# Ring_opto_interface_v2.net
KiCad netlist of a schematic drawn in EAGLE
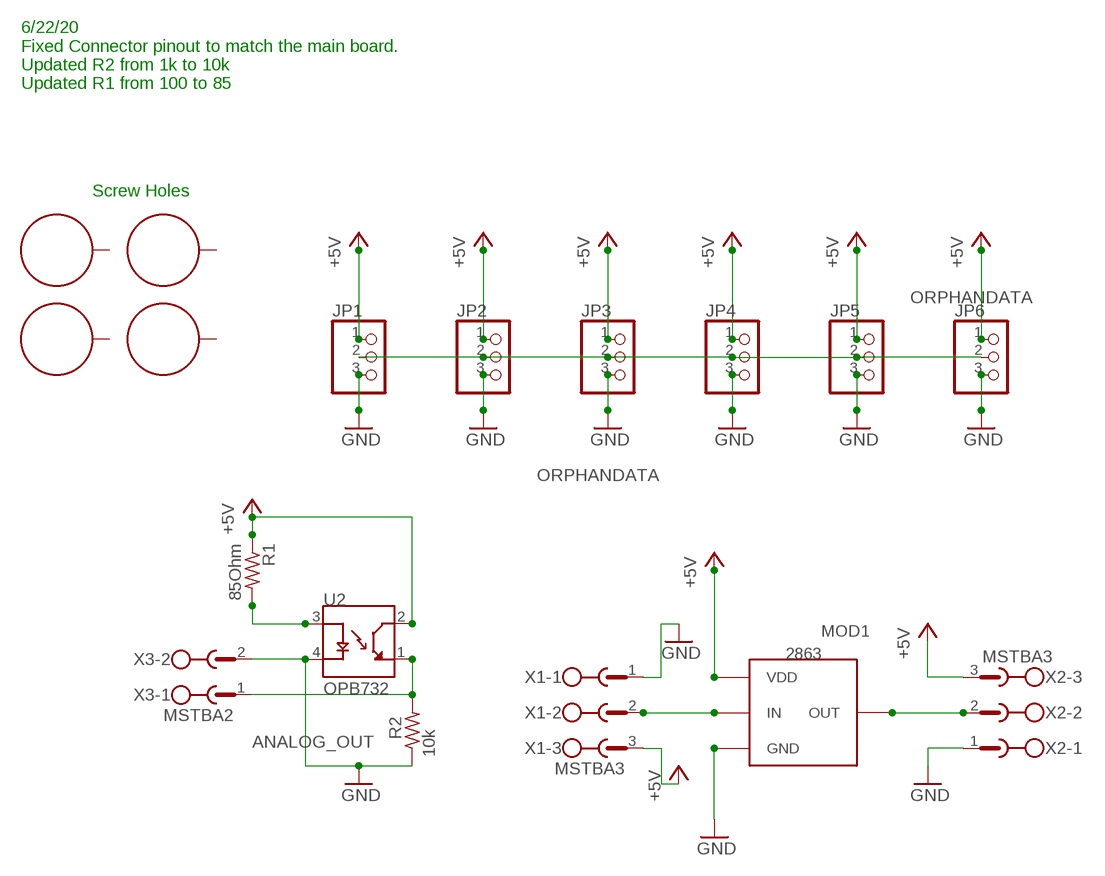
[diagram p0: schematic, sheet 1]

(export (version "E")
  (design (tool "Eeschema 10.0.6"))
  (components
    (comp (ref "H1")
      (value "STANDOFF_ELECTRICAL5-32")
      (footprint "eagle-import:STANDOFF_ELECTRICAL_5_32")
      (libsource (lib "eagle-import") (part "STANDOFF_ELECTRICAL5-32"))
    )
    (comp (ref "H2")
      (value "STANDOFF_ELECTRICAL5-32")
      (footprint "eagle-import:STANDOFF_ELECTRICAL_5_32")
      (libsource (lib "eagle-import") (part "STANDOFF_ELECTRICAL5-32"))
    )
    (comp (ref "H3")
      (value "STANDOFF_ELECTRICAL5-32")
      (footprint "eagle-import:STANDOFF_ELECTRICAL_5_32")
      (libsource (lib "eagle-import") (part "STANDOFF_ELECTRICAL5-32"))
    )
    (comp (ref "H4")
      (value "STANDOFF_ELECTRICAL5-32")
      (footprint "eagle-import:STANDOFF_ELECTRICAL_5_32")
      (libsource (lib "eagle-import") (part "STANDOFF_ELECTRICAL5-32"))
    )
    (comp (ref "JP1")
      (value "PINHD-1X3CB")
      (footprint "eagle-import:1X03-CLEANBIG")
      (libsource (lib "eagle-import") (part "PINHD-1X3CB"))
    )
    (comp (ref "JP2")
      (value "PINHD-1X3CB")
      (footprint "eagle-import:1X03-CLEANBIG")
      (libsource (lib "eagle-import") (part "PINHD-1X3CB"))
    )
    (comp (ref "JP3")
      (value "PINHD-1X3CB")
      (footprint "eagle-import:1X03-CLEANBIG")
      (libsource (lib "eagle-import") (part "PINHD-1X3CB"))
    )
    (comp (ref "JP4")
      (value "PINHD-1X3CB")
      (footprint "eagle-import:1X03-CLEANBIG")
      (libsource (lib "eagle-import") (part "PINHD-1X3CB"))
    )
    (comp (ref "JP5")
      (value "PINHD-1X3CB")
      (footprint "eagle-import:1X03-CLEANBIG")
      (libsource (lib "eagle-import") (part "PINHD-1X3CB"))
    )
    (comp (ref "JP6")
      (value "PINHD-1X3CB")
      (footprint "eagle-import:1X03-CLEANBIG")
      (libsource (lib "eagle-import") (part "PINHD-1X3CB"))
    )
    (comp (ref "MOD1")
      (value "2863")
      (footprint "eagle-import:ADAFRUIT_2863")
      (fields (field (name "MF") "Adafruit"))
      (libsource (lib "eagle-import") (part "2863"))
    )
    (comp (ref "R1")
      (value "85Ohm")
      (footprint "eagle-import:RESAD1176W63L850D250B")
      (libsource (lib "eagle-import") (part "R-USAXIAL-11.7MM-PITCH_"))
    )
    (comp (ref "R2")
      (value "10k")
      (footprint "eagle-import:RESAD1176W63L850D250B")
      (libsource (lib "eagle-import") (part "R-USAXIAL-11.7MM-PITCH_"))
    )
    (comp (ref "U2")
      (value "OPB732")
      (footprint "eagle-import:OPTO_OPB732")
      (fields (field (name "MF") "TT Electronics/Optek"))
      (libsource (lib "eagle-import") (part "OPB732"))
    )
    (comp (ref "X1")
      (value "MSTBA3")
      (footprint "eagle-import:MSTBA3")
      (fields (field (name "MF") "FARNELL") (field (name "MPN") "1757255"))
      (libsource (lib "eagle-import") (part "MSTBA3"))
    )
    (comp (ref "X2")
      (value "MSTBA3")
      (footprint "eagle-import:MSTBA3")
      (fields (field (name "MF") "FARNELL") (field (name "MPN") "1757255"))
      (libsource (lib "eagle-import") (part "MSTBA3"))
    )
    (comp (ref "X3")
      (value "MSTBA2")
      (footprint "eagle-import:MSTBA2")
      (fields (field (name "MF") "FARNELL") (field (name "MPN") "1757242"))
      (libsource (lib "eagle-import") (part "MSTBA2"))
    )
  )
  (nets
    (net (code "1") (name "+5V") (class "Default")
      (node (ref "JP1") (pin "1") (pinfunction "1_1") (pintype "passive"))
      (node (ref "JP2") (pin "1") (pinfunction "1_1") (pintype "passive"))
      (node (ref "JP3") (pin "1") (pinfunction "1_1") (pintype "passive"))
      (node (ref "JP4") (pin "1") (pinfunction "1_1") (pintype "passive"))
      (node (ref "JP5") (pin "1") (pinfunction "1_1") (pintype "passive"))
      (node (ref "JP6") (pin "1") (pinfunction "1_1") (pintype "passive"))
      (node (ref "MOD1") (pin "VDD1") (pinfunction "VDD_VDD1") (pintype "power_in"))
      (node (ref "MOD1") (pin "VDD2") (pinfunction "VDD_VDD2") (pintype "power_in"))
      (node (ref "R1") (pin "1") (pinfunction "1_1") (pintype "passive"))
      (node (ref "U2") (pin "2") (pinfunction "CT_2") (pintype "passive"))
      (node (ref "X1") (pin "3") (pinfunction "1_3") (pintype "passive"))
      (node (ref "X2") (pin "3") (pinfunction "1_3") (pintype "passive"))
    )
    (net (code "2") (name "/ANALOG_OUT") (class "Default")
      (node (ref "R2") (pin "2") (pinfunction "2_2") (pintype "passive"))
      (node (ref "U2") (pin "1") (pinfunction "ET_1") (pintype "passive"))
      (node (ref "X3") (pin "1") (pinfunction "1_1") (pintype "passive"))
    )
    (net (code "3") (name "/ORPHANDATA") (class "Default")
      (node (ref "JP1") (pin "2") (pinfunction "2_2") (pintype "passive"))
      (node (ref "JP2") (pin "2") (pinfunction "2_2") (pintype "passive"))
      (node (ref "JP3") (pin "2") (pinfunction "2_2") (pintype "passive"))
      (node (ref "JP4") (pin "2") (pinfunction "2_2") (pintype "passive"))
      (node (ref "JP5") (pin "2") (pinfunction "2_2") (pintype "passive"))
      (node (ref "JP6") (pin "2") (pinfunction "2_2") (pintype "passive"))
    )
    (net (code "4") (name "GND") (class "Default")
      (node (ref "JP1") (pin "3") (pinfunction "3_3") (pintype "passive"))
      (node (ref "JP2") (pin "3") (pinfunction "3_3") (pintype "passive"))
      (node (ref "JP3") (pin "3") (pinfunction "3_3") (pintype "passive"))
      (node (ref "JP4") (pin "3") (pinfunction "3_3") (pintype "passive"))
      (node (ref "JP5") (pin "3") (pinfunction "3_3") (pintype "passive"))
      (node (ref "JP6") (pin "3") (pinfunction "3_3") (pintype "passive"))
      (node (ref "MOD1") (pin "GND1") (pinfunction "GND_GND1") (pintype "power_in"))
      (node (ref "MOD1") (pin "GND2") (pinfunction "GND_GND2") (pintype "power_in"))
      (node (ref "R2") (pin "1") (pinfunction "1_1") (pintype "passive"))
      (node (ref "U2") (pin "4") (pinfunction "C_4") (pintype "passive"))
      (node (ref "X1") (pin "1") (pinfunction "1_1") (pintype "passive"))
      (node (ref "X2") (pin "1") (pinfunction "1_1") (pintype "passive"))
      (node (ref "X3") (pin "2") (pinfunction "1_2") (pintype "passive"))
    )
    (net (code "5") (name "Net-(U2-A)") (class "Default")
      (node (ref "R1") (pin "2") (pinfunction "2_2") (pintype "passive"))
      (node (ref "U2") (pin "3") (pinfunction "A_3") (pintype "passive"))
    )
    (net (code "6") (name "Net-(X1B-1)") (class "Default")
      (node (ref "MOD1") (pin "IN") (pinfunction "IN_IN") (pintype "input"))
      (node (ref "X1") (pin "2") (pinfunction "1_2") (pintype "passive"))
    )
    (net (code "7") (name "Net-(X2B-1)") (class "Default")
      (node (ref "MOD1") (pin "OUT") (pinfunction "OUT_OUT") (pintype "output"))
      (node (ref "X2") (pin "2") (pinfunction "1_2") (pintype "passive"))
    )
    (net (code "8") (name "unconnected-(H1-P$1-PadP1)") (class "Default")
      (node (ref "H1") (pin "P1") (pinfunction "P$1_P1") (pintype "bidirectional"))
    )
    (net (code "9") (name "unconnected-(H2-P$1-PadP1)") (class "Default")
      (node (ref "H2") (pin "P1") (pinfunction "P$1_P1") (pintype "bidirectional"))
    )
    (net (code "10") (name "unconnected-(H3-P$1-PadP1)") (class "Default")
      (node (ref "H3") (pin "P1") (pinfunction "P$1_P1") (pintype "bidirectional"))
    )
    (net (code "11") (name "unconnected-(H4-P$1-PadP1)") (class "Default")
      (node (ref "H4") (pin "P1") (pinfunction "P$1_P1") (pintype "bidirectional"))
    )
  )
)
